# usb2ax_pro_main_v1_0.net
KiCad netlist of a schematic drawn in EAGLE
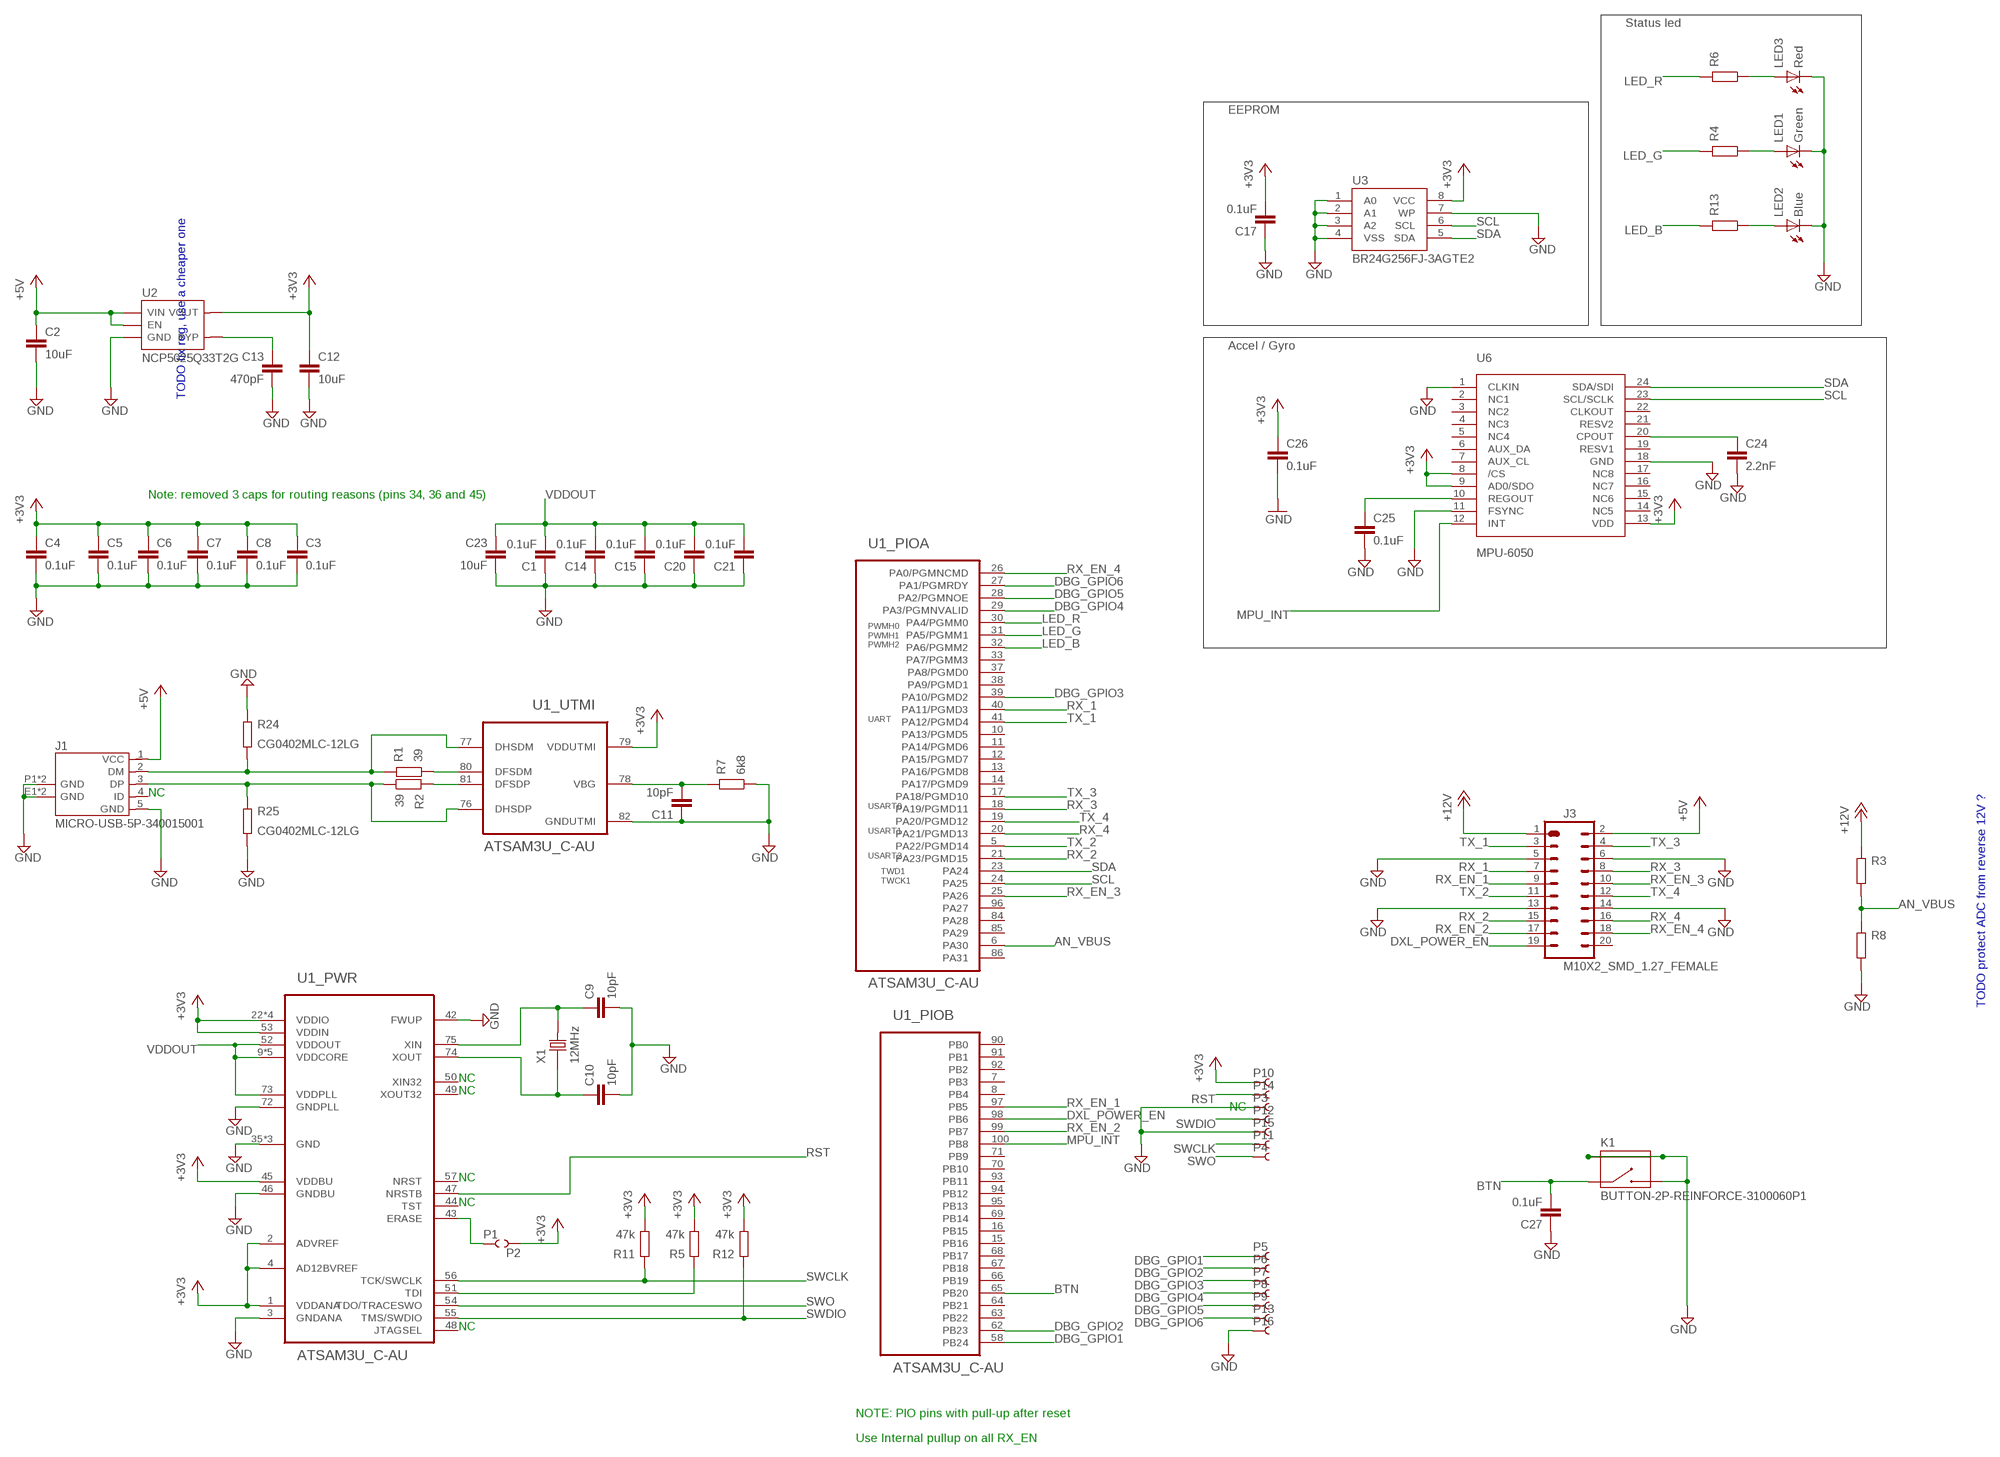
[diagram p0: schematic, sheet 1]

(export (version "E")
  (design (tool "Eeschema 10.0.6"))
  (components
    (comp (ref "C1")
      (value "0.1uF")
      (footprint "eagle-import:0201_N")
      (libsource (lib "eagle-import") (part "C0201"))
    )
    (comp (ref "C2")
      (value "10uF")
      (footprint "eagle-import:0805_N")
      (libsource (lib "eagle-import") (part "C0805"))
    )
    (comp (ref "C3")
      (value "0.1uF")
      (footprint "eagle-import:0201_N")
      (libsource (lib "eagle-import") (part "C0201"))
    )
    (comp (ref "C4")
      (value "0.1uF")
      (footprint "eagle-import:0201_N")
      (libsource (lib "eagle-import") (part "C0201"))
    )
    (comp (ref "C5")
      (value "0.1uF")
      (footprint "eagle-import:0201_N")
      (libsource (lib "eagle-import") (part "C0201"))
    )
    (comp (ref "C6")
      (value "0.1uF")
      (footprint "eagle-import:0201_N")
      (libsource (lib "eagle-import") (part "C0201"))
    )
    (comp (ref "C7")
      (value "0.1uF")
      (footprint "eagle-import:0201_N")
      (libsource (lib "eagle-import") (part "C0201"))
    )
    (comp (ref "C8")
      (value "0.1uF")
      (footprint "eagle-import:0201_N")
      (libsource (lib "eagle-import") (part "C0201"))
    )
    (comp (ref "C9")
      (value "10pF")
      (footprint "eagle-import:0201_N")
      (libsource (lib "eagle-import") (part "C0201"))
    )
    (comp (ref "C10")
      (value "10pF")
      (footprint "eagle-import:0201_N")
      (libsource (lib "eagle-import") (part "C0201"))
    )
    (comp (ref "C11")
      (value "10pF")
      (footprint "eagle-import:0201_N")
      (libsource (lib "eagle-import") (part "C0201"))
    )
    (comp (ref "C12")
      (value "10uF")
      (footprint "eagle-import:0805_N")
      (libsource (lib "eagle-import") (part "C0805"))
    )
    (comp (ref "C13")
      (value "470pF")
      (footprint "eagle-import:0201_N")
      (libsource (lib "eagle-import") (part "C0201"))
    )
    (comp (ref "C14")
      (value "0.1uF")
      (footprint "eagle-import:0201_N")
      (libsource (lib "eagle-import") (part "C0201"))
    )
    (comp (ref "C15")
      (value "0.1uF")
      (footprint "eagle-import:0201_N")
      (libsource (lib "eagle-import") (part "C0201"))
    )
    (comp (ref "C17")
      (value "0.1uF")
      (footprint "eagle-import:0201_N")
      (libsource (lib "eagle-import") (part "C0201"))
    )
    (comp (ref "C20")
      (value "0.1uF")
      (footprint "eagle-import:0201_N")
      (libsource (lib "eagle-import") (part "C0201"))
    )
    (comp (ref "C21")
      (value "0.1uF")
      (footprint "eagle-import:0201_N")
      (libsource (lib "eagle-import") (part "C0201"))
    )
    (comp (ref "C23")
      (value "10uF")
      (footprint "eagle-import:0805_N")
      (libsource (lib "eagle-import") (part "C0805"))
    )
    (comp (ref "C24")
      (value "2.2nF")
      (footprint "eagle-import:0201_N")
      (libsource (lib "eagle-import") (part "C0201"))
    )
    (comp (ref "C25")
      (value "0.1uF")
      (footprint "eagle-import:0201_N")
      (libsource (lib "eagle-import") (part "C0201"))
    )
    (comp (ref "C26")
      (value "0.1uF")
      (footprint "eagle-import:0201_N")
      (libsource (lib "eagle-import") (part "C0201"))
    )
    (comp (ref "C27")
      (value "0.1uF")
      (footprint "eagle-import:0201_N")
      (libsource (lib "eagle-import") (part "C0201"))
    )
    (comp (ref "J1")
      (value "MICRO-USB-5P-340015001")
      (footprint "eagle-import:B-SMD-5P")
      (libsource (lib "eagle-import") (part "MICRO-USB-5P-340015001"))
    )
    (comp (ref "J3")
      (value "M10X2_SMD_1.27_FEMALE")
      (footprint "eagle-import:2X10_SMD_1.27_FEMALE")
      (libsource (lib "eagle-import") (part "M10X2_SMD_1.27_FEMALE"))
    )
    (comp (ref "K1")
      (value "BUTTON-2P-REINFORCE-3100060P1")
      (footprint "eagle-import:4P-SMD-7.0X3.5X3.5H-90D")
      (libsource (lib "eagle-import") (part "BUTTON-2P-REINFORCE-3100060P1"))
    )
    (comp (ref "LED1")
      (value "Green")
      (footprint "eagle-import:D_0603_N")
      (libsource (lib "eagle-import") (part "LED0603"))
    )
    (comp (ref "LED2")
      (value "Blue")
      (footprint "eagle-import:D_0603_N")
      (libsource (lib "eagle-import") (part "LED0603"))
    )
    (comp (ref "LED3")
      (value "Red")
      (footprint "eagle-import:D_0603_N")
      (libsource (lib "eagle-import") (part "LED0603"))
    )
    (comp (ref "P1")
      (value "PIN_SMD_2X2.5")
      (footprint "eagle-import:PIN_SMD_2X2.5")
      (libsource (lib "eagle-import") (part "PIN_SMD_2X2.5"))
    )
    (comp (ref "P2")
      (value "PIN_SMD_2X2.5")
      (footprint "eagle-import:PIN_SMD_2X2.5")
      (libsource (lib "eagle-import") (part "PIN_SMD_2X2.5"))
    )
    (comp (ref "P3")
      (value "PIN_SMD_0.8X1.6")
      (footprint "eagle-import:PIN_SMD_0.8X1.6")
      (libsource (lib "eagle-import") (part "PIN_SMD_0.8X1.6"))
    )
    (comp (ref "P4")
      (value "PIN_SMD_0.8X1.6")
      (footprint "eagle-import:PIN_SMD_0.8X1.6")
      (libsource (lib "eagle-import") (part "PIN_SMD_0.8X1.6"))
    )
    (comp (ref "P5")
      (value "PIN_SMD_1X2")
      (footprint "eagle-import:PIN_SMD_1X2")
      (libsource (lib "eagle-import") (part "PIN_SMD_1X2"))
    )
    (comp (ref "P6")
      (value "PIN_SMD_1X2")
      (footprint "eagle-import:PIN_SMD_1X2")
      (libsource (lib "eagle-import") (part "PIN_SMD_1X2"))
    )
    (comp (ref "P7")
      (value "PIN_SMD_1X2")
      (footprint "eagle-import:PIN_SMD_1X2")
      (libsource (lib "eagle-import") (part "PIN_SMD_1X2"))
    )
    (comp (ref "P8")
      (value "PIN_SMD_1X2")
      (footprint "eagle-import:PIN_SMD_1X2")
      (libsource (lib "eagle-import") (part "PIN_SMD_1X2"))
    )
    (comp (ref "P9")
      (value "PIN_SMD_1X2")
      (footprint "eagle-import:PIN_SMD_1X2")
      (libsource (lib "eagle-import") (part "PIN_SMD_1X2"))
    )
    (comp (ref "P10")
      (value "PIN_SMD_0.8X1.6")
      (footprint "eagle-import:PIN_SMD_0.8X1.6")
      (libsource (lib "eagle-import") (part "PIN_SMD_0.8X1.6"))
    )
    (comp (ref "P11")
      (value "PIN_SMD_0.8X1.6")
      (footprint "eagle-import:PIN_SMD_0.8X1.6")
      (libsource (lib "eagle-import") (part "PIN_SMD_0.8X1.6"))
    )
    (comp (ref "P12")
      (value "PIN_SMD_0.8X1.6")
      (footprint "eagle-import:PIN_SMD_0.8X1.6")
      (libsource (lib "eagle-import") (part "PIN_SMD_0.8X1.6"))
    )
    (comp (ref "P13")
      (value "PIN_SMD_1X2")
      (footprint "eagle-import:PIN_SMD_1X2")
      (libsource (lib "eagle-import") (part "PIN_SMD_1X2"))
    )
    (comp (ref "P14")
      (value "PIN_SMD_0.8X1.6")
      (footprint "eagle-import:PIN_SMD_0.8X1.6")
      (libsource (lib "eagle-import") (part "PIN_SMD_0.8X1.6"))
    )
    (comp (ref "P15")
      (value "PIN_SMD_0.8X1.6")
      (footprint "eagle-import:PIN_SMD_0.8X1.6")
      (libsource (lib "eagle-import") (part "PIN_SMD_0.8X1.6"))
    )
    (comp (ref "P16")
      (value "PIN_SMD_1X2")
      (footprint "eagle-import:PIN_SMD_1X2")
      (libsource (lib "eagle-import") (part "PIN_SMD_1X2"))
    )
    (comp (ref "R1")
      (value "39")
      (footprint "eagle-import:0201_N")
      (libsource (lib "eagle-import") (part "R0201"))
    )
    (comp (ref "R2")
      (value "39")
      (footprint "eagle-import:0201_N")
      (libsource (lib "eagle-import") (part "R0201"))
    )
    (comp (ref "R3")
      (value "R0201")
      (footprint "eagle-import:0201_N")
      (libsource (lib "eagle-import") (part "R0201"))
    )
    (comp (ref "R4")
      (value "R0201")
      (footprint "eagle-import:0201_N")
      (libsource (lib "eagle-import") (part "R0201"))
    )
    (comp (ref "R5")
      (value "47k")
      (footprint "eagle-import:0201_N")
      (libsource (lib "eagle-import") (part "R0201"))
    )
    (comp (ref "R6")
      (value "R0201")
      (footprint "eagle-import:0201_N")
      (libsource (lib "eagle-import") (part "R0201"))
    )
    (comp (ref "R7")
      (value "6k8")
      (footprint "eagle-import:0201_N")
      (libsource (lib "eagle-import") (part "R0201"))
    )
    (comp (ref "R8")
      (value "R0201")
      (footprint "eagle-import:0201_N")
      (libsource (lib "eagle-import") (part "R0201"))
    )
    (comp (ref "R11")
      (value "47k")
      (footprint "eagle-import:0201_N")
      (libsource (lib "eagle-import") (part "R0201"))
    )
    (comp (ref "R12")
      (value "47k")
      (footprint "eagle-import:0201_N")
      (libsource (lib "eagle-import") (part "R0201"))
    )
    (comp (ref "R13")
      (value "R0201")
      (footprint "eagle-import:0201_N")
      (libsource (lib "eagle-import") (part "R0201"))
    )
    (comp (ref "R24")
      (value "CG0402MLC-12LG")
      (footprint "eagle-import:0402_N")
      (libsource (lib "eagle-import") (part "R0402"))
    )
    (comp (ref "R25")
      (value "CG0402MLC-12LG")
      (footprint "eagle-import:0402_N")
      (libsource (lib "eagle-import") (part "R0402"))
    )
    (comp (ref "U1")
      (value "ATSAM3U_C-AU")
      (footprint "eagle-import:QFP50P1600X1600-100N")
      (libsource (lib "eagle-import") (part "ATSAM3U_C-AU"))
    )
    (comp (ref "U2")
      (value "NCP5025Q33T2G")
      (footprint "eagle-import:SC70-5")
      (libsource (lib "eagle-import") (part "MIC5205-3.3YM5"))
    )
    (comp (ref "U3")
      (value "BR24G256FJ-3AGTE2")
      (footprint "eagle-import:SO08")
      (libsource (lib "eagle-import") (part "EEPROM-I2CSMD"))
    )
    (comp (ref "U6")
      (value "MPU-6050")
      (footprint "eagle-import:QFN-24")
      (libsource (lib "eagle-import") (part "MPU-6000"))
    )
    (comp (ref "X1")
      (value "12MHz")
      (footprint "eagle-import:2P-SMD-5.0X3.2")
      (libsource (lib "eagle-import") (part "CRYSTAL-0500290P1"))
    )
  )
  (nets
    (net (code "1") (name "+3V3") (class "Default")
      (node (ref "C12") (pin "1") (pinfunction "1_1") (pintype "passive"))
      (node (ref "C17") (pin "2") (pinfunction "2_2") (pintype "passive"))
      (node (ref "C26") (pin "1") (pinfunction "1_1") (pintype "passive"))
      (node (ref "C3") (pin "1") (pinfunction "1_1") (pintype "passive"))
      (node (ref "C4") (pin "1") (pinfunction "1_1") (pintype "passive"))
      (node (ref "C5") (pin "1") (pinfunction "1_1") (pintype "passive"))
      (node (ref "C6") (pin "1") (pinfunction "1_1") (pintype "passive"))
      (node (ref "C7") (pin "1") (pinfunction "1_1") (pintype "passive"))
      (node (ref "C8") (pin "1") (pinfunction "1_1") (pintype "passive"))
      (node (ref "P10") (pin "PIN") (pinfunction "1_PIN") (pintype "bidirectional"))
      (node (ref "P2") (pin "PIN") (pinfunction "1_PIN") (pintype "bidirectional"))
      (node (ref "R11") (pin "1") (pinfunction "1_1") (pintype "passive"))
      (node (ref "R12") (pin "1") (pinfunction "1_1") (pintype "passive"))
      (node (ref "R5") (pin "1") (pinfunction "1_1") (pintype "passive"))
      (node (ref "U1") (pin "1") (pinfunction "VDDANA_1") (pintype "power_in"))
      (node (ref "U1") (pin "2") (pinfunction "ADVREF_2") (pintype "input"))
      (node (ref "U1") (pin "22") (pinfunction "VDDIO_22") (pintype "power_in"))
      (node (ref "U1") (pin "36") (pinfunction "VDDIO_36") (pintype "power_in"))
      (node (ref "U1") (pin "4") (pinfunction "AD12BVREF_4") (pintype "passive"))
      (node (ref "U1") (pin "45") (pinfunction "VDDBU_45") (pintype "power_in"))
      (node (ref "U1") (pin "53") (pinfunction "VDDIN_53") (pintype "power_in"))
      (node (ref "U1") (pin "60") (pinfunction "VDDIO_60") (pintype "power_in"))
      (node (ref "U1") (pin "79") (pinfunction "VDDUTMI_79") (pintype "power_in"))
      (node (ref "U1") (pin "88") (pinfunction "VDDIO_88") (pintype "power_in"))
      (node (ref "U2") (pin "5") (pinfunction "VOUT_5") (pintype "bidirectional"))
      (node (ref "U3") (pin "8") (pinfunction "VCC_8") (pintype "power_in"))
      (node (ref "U6") (pin "13") (pinfunction "VDD_13") (pintype "bidirectional"))
      (node (ref "U6") (pin "8") (pinfunction "/CS_8") (pintype "bidirectional"))
      (node (ref "U6") (pin "9") (pinfunction "AD0/SDO_9") (pintype "bidirectional"))
    )
    (net (code "2") (name "+5V") (class "Default")
      (node (ref "C2") (pin "1") (pinfunction "1_1") (pintype "passive"))
      (node (ref "J1") (pin "1") (pinfunction "VCC_1") (pintype "bidirectional"))
      (node (ref "J3") (pin "2") (pinfunction "2_2") (pintype "passive"))
      (node (ref "U2") (pin "1") (pinfunction "VIN_1") (pintype "bidirectional"))
      (node (ref "U2") (pin "3") (pinfunction "EN_3") (pintype "bidirectional"))
    )
    (net (code "3") (name "+12V") (class "Default")
      (node (ref "J3") (pin "1") (pinfunction "1_1") (pintype "passive"))
      (node (ref "R3") (pin "2") (pinfunction "2_2") (pintype "passive"))
    )
    (net (code "4") (name "/AN_VBUS") (class "Default")
      (node (ref "R3") (pin "1") (pinfunction "1_1") (pintype "passive"))
      (node (ref "R8") (pin "2") (pinfunction "2_2") (pintype "passive"))
      (node (ref "U1") (pin "6") (pinfunction "PA30_6") (pintype "bidirectional"))
    )
    (net (code "5") (name "/BTN") (class "Default")
      (node (ref "C27") (pin "2") (pinfunction "2_2") (pintype "passive"))
      (node (ref "K1") (pin "1") (pinfunction "1_1") (pintype "bidirectional"))
      (node (ref "U1") (pin "65") (pinfunction "PB20_65") (pintype "bidirectional"))
    )
    (net (code "6") (name "/DBG_GPIO1") (class "Default")
      (node (ref "P5") (pin "P$1") (pinfunction "1_P$1") (pintype "bidirectional"))
      (node (ref "U1") (pin "58") (pinfunction "PB24_58") (pintype "bidirectional"))
    )
    (net (code "7") (name "/DBG_GPIO2") (class "Default")
      (node (ref "P6") (pin "P$1") (pinfunction "1_P$1") (pintype "bidirectional"))
      (node (ref "U1") (pin "62") (pinfunction "PB23_62") (pintype "bidirectional"))
    )
    (net (code "8") (name "/DBG_GPIO3") (class "Default")
      (node (ref "P7") (pin "P$1") (pinfunction "1_P$1") (pintype "bidirectional"))
      (node (ref "U1") (pin "39") (pinfunction "PA10/PGMD2_39") (pintype "bidirectional"))
    )
    (net (code "9") (name "/DBG_GPIO4") (class "Default")
      (node (ref "P8") (pin "P$1") (pinfunction "1_P$1") (pintype "bidirectional"))
      (node (ref "U1") (pin "29") (pinfunction "PA3/PGMNVALID_29") (pintype "bidirectional"))
    )
    (net (code "10") (name "/DBG_GPIO5") (class "Default")
      (node (ref "P9") (pin "P$1") (pinfunction "1_P$1") (pintype "bidirectional"))
      (node (ref "U1") (pin "28") (pinfunction "PA2/PGMNOE_28") (pintype "bidirectional"))
    )
    (net (code "11") (name "/DBG_GPIO6") (class "Default")
      (node (ref "P13") (pin "P$1") (pinfunction "1_P$1") (pintype "bidirectional"))
      (node (ref "U1") (pin "27") (pinfunction "PA1/PGMRDY_27") (pintype "bidirectional"))
    )
    (net (code "12") (name "/DXL_POWER_EN") (class "Default")
      (node (ref "J3") (pin "19") (pinfunction "19_19") (pintype "passive"))
      (node (ref "U1") (pin "98") (pinfunction "PB6_98") (pintype "bidirectional"))
    )
    (net (code "13") (name "/LED_B") (class "Default")
      (node (ref "R13") (pin "2") (pinfunction "2_2") (pintype "passive"))
      (node (ref "U1") (pin "32") (pinfunction "PA6/PGMM2_32") (pintype "bidirectional"))
    )
    (net (code "14") (name "/LED_G") (class "Default")
      (node (ref "R4") (pin "2") (pinfunction "2_2") (pintype "passive"))
      (node (ref "U1") (pin "31") (pinfunction "PA5/PGMM1_31") (pintype "bidirectional"))
    )
    (net (code "15") (name "/LED_R") (class "Default")
      (node (ref "R6") (pin "2") (pinfunction "2_2") (pintype "passive"))
      (node (ref "U1") (pin "30") (pinfunction "PA4/PGMM0_30") (pintype "bidirectional"))
    )
    (net (code "16") (name "/MPU_INT") (class "Default")
      (node (ref "U1") (pin "100") (pinfunction "PB8_100") (pintype "bidirectional"))
      (node (ref "U6") (pin "12") (pinfunction "INT_12") (pintype "bidirectional"))
    )
    (net (code "17") (name "/RST") (class "Default")
      (node (ref "P14") (pin "PIN") (pinfunction "1_PIN") (pintype "bidirectional"))
      (node (ref "U1") (pin "47") (pinfunction "NRSTB_47") (pintype "input"))
    )
    (net (code "18") (name "/RX_1") (class "Default")
      (node (ref "J3") (pin "7") (pinfunction "7_7") (pintype "passive"))
      (node (ref "U1") (pin "40") (pinfunction "PA11/PGMD3_40") (pintype "bidirectional"))
    )
    (net (code "19") (name "/RX_2") (class "Default")
      (node (ref "J3") (pin "15") (pinfunction "15_15") (pintype "passive"))
      (node (ref "U1") (pin "21") (pinfunction "PA23/PGMD15_21") (pintype "bidirectional"))
    )
    (net (code "20") (name "/RX_3") (class "Default")
      (node (ref "J3") (pin "8") (pinfunction "8_8") (pintype "passive"))
      (node (ref "U1") (pin "18") (pinfunction "PA19/PGMD11_18") (pintype "bidirectional"))
    )
    (net (code "21") (name "/RX_4") (class "Default")
      (node (ref "J3") (pin "16") (pinfunction "16_16") (pintype "passive"))
      (node (ref "U1") (pin "20") (pinfunction "PA21/PGMD13_20") (pintype "bidirectional"))
    )
    (net (code "22") (name "/RX_EN_1") (class "Default")
      (node (ref "J3") (pin "9") (pinfunction "9_9") (pintype "passive"))
      (node (ref "U1") (pin "97") (pinfunction "PB5_97") (pintype "bidirectional"))
    )
    (net (code "23") (name "/RX_EN_2") (class "Default")
      (node (ref "J3") (pin "17") (pinfunction "17_17") (pintype "passive"))
      (node (ref "U1") (pin "99") (pinfunction "PB7_99") (pintype "bidirectional"))
    )
    (net (code "24") (name "/RX_EN_3") (class "Default")
      (node (ref "J3") (pin "10") (pinfunction "10_10") (pintype "passive"))
      (node (ref "U1") (pin "25") (pinfunction "PA26_25") (pintype "bidirectional"))
    )
    (net (code "25") (name "/RX_EN_4") (class "Default")
      (node (ref "J3") (pin "18") (pinfunction "18_18") (pintype "passive"))
      (node (ref "U1") (pin "26") (pinfunction "PA0/PGMNCMD_26") (pintype "bidirectional"))
    )
    (net (code "26") (name "/SCL") (class "Default")
      (node (ref "U1") (pin "24") (pinfunction "PA25_24") (pintype "bidirectional"))
      (node (ref "U3") (pin "6") (pinfunction "SCL_6") (pintype "bidirectional"))
      (node (ref "U6") (pin "23") (pinfunction "SCL/SCLK_23") (pintype "bidirectional"))
    )
    (net (code "27") (name "/SDA") (class "Default")
      (node (ref "U1") (pin "23") (pinfunction "PA24_23") (pintype "bidirectional"))
      (node (ref "U3") (pin "5") (pinfunction "SDA_5") (pintype "bidirectional"))
      (node (ref "U6") (pin "24") (pinfunction "SDA/SDI_24") (pintype "bidirectional"))
    )
    (net (code "28") (name "/SWCLK") (class "Default")
      (node (ref "P11") (pin "PIN") (pinfunction "1_PIN") (pintype "bidirectional"))
      (node (ref "R11") (pin "2") (pinfunction "2_2") (pintype "passive"))
      (node (ref "U1") (pin "56") (pinfunction "TCK/SWCLK_56") (pintype "input"))
    )
    (net (code "29") (name "/SWDIO") (class "Default")
      (node (ref "P12") (pin "PIN") (pinfunction "1_PIN") (pintype "bidirectional"))
      (node (ref "R12") (pin "2") (pinfunction "2_2") (pintype "passive"))
      (node (ref "U1") (pin "55") (pinfunction "TMS/SWDIO_55") (pintype "bidirectional"))
    )
    (net (code "30") (name "/SWO") (class "Default")
      (node (ref "P4") (pin "PIN") (pinfunction "1_PIN") (pintype "bidirectional"))
      (node (ref "U1") (pin "54") (pinfunction "TDO/TRACESWO_54") (pintype "output"))
    )
    (net (code "31") (name "/TX_1") (class "Default")
      (node (ref "J3") (pin "3") (pinfunction "3_3") (pintype "passive"))
      (node (ref "U1") (pin "41") (pinfunction "PA12/PGMD4_41") (pintype "bidirectional"))
    )
    (net (code "32") (name "/TX_2") (class "Default")
      (node (ref "J3") (pin "11") (pinfunction "11_11") (pintype "passive"))
      (node (ref "U1") (pin "5") (pinfunction "PA22/PGMD14_5") (pintype "bidirectional"))
    )
    (net (code "33") (name "/TX_3") (class "Default")
      (node (ref "J3") (pin "4") (pinfunction "4_4") (pintype "passive"))
      (node (ref "U1") (pin "17") (pinfunction "PA18/PGMD10_17") (pintype "bidirectional"))
    )
    (net (code "34") (name "/TX_4") (class "Default")
      (node (ref "J3") (pin "12") (pinfunction "12_12") (pintype "passive"))
      (node (ref "U1") (pin "19") (pinfunction "PA20/PGMD12_19") (pintype "bidirectional"))
    )
    (net (code "35") (name "/VDDOUT") (class "Default")
      (node (ref "C1") (pin "2") (pinfunction "2_2") (pintype "passive"))
      (node (ref "C14") (pin "2") (pinfunction "2_2") (pintype "passive"))
      (node (ref "C15") (pin "2") (pinfunction "2_2") (pintype "passive"))
      (node (ref "C20") (pin "2") (pinfunction "2_2") (pintype "passive"))
      (node (ref "C21") (pin "2") (pinfunction "2_2") (pintype "passive"))
      (node (ref "C23") (pin "1") (pinfunction "1_1") (pintype "passive"))
      (node (ref "U1") (pin "34") (pinfunction "VDDCORE_34") (pintype "power_in"))
      (node (ref "U1") (pin "52") (pinfunction "VDDOUT_52") (pintype "power_in"))
      (node (ref "U1") (pin "59") (pinfunction "VDDCORE_59") (pintype "power_in"))
      (node (ref "U1") (pin "73") (pinfunction "VDDPLL_73") (pintype "power_in"))
      (node (ref "U1") (pin "83") (pinfunction "VDDCORE_83") (pintype "power_in"))
      (node (ref "U1") (pin "87") (pinfunction "VDDCORE_87") (pintype "power_in"))
      (node (ref "U1") (pin "9") (pinfunction "VDDCORE_9") (pintype "power_in"))
    )
    (net (code "36") (name "GND") (class "Default")
      (node (ref "C1") (pin "1") (pinfunction "1_1") (pintype "passive"))
      (node (ref "C10") (pin "2") (pinfunction "2_2") (pintype "passive"))
      (node (ref "C11") (pin "1") (pinfunction "1_1") (pintype "passive"))
      (node (ref "C12") (pin "2") (pinfunction "2_2") (pintype "passive"))
      (node (ref "C13") (pin "2") (pinfunction "2_2") (pintype "passive"))
      (node (ref "C14") (pin "1") (pinfunction "1_1") (pintype "passive"))
      (node (ref "C15") (pin "1") (pinfunction "1_1") (pintype "passive"))
      (node (ref "C17") (pin "1") (pinfunction "1_1") (pintype "passive"))
      (node (ref "C2") (pin "2") (pinfunction "2_2") (pintype "passive"))
      (node (ref "C20") (pin "1") (pinfunction "1_1") (pintype "passive"))
      (node (ref "C21") (pin "1") (pinfunction "1_1") (pintype "passive"))
      (node (ref "C23") (pin "2") (pinfunction "2_2") (pintype "passive"))
      (node (ref "C24") (pin "2") (pinfunction "2_2") (pintype "passive"))
      (node (ref "C25") (pin "2") (pinfunction "2_2") (pintype "passive"))
      (node (ref "C26") (pin "2") (pinfunction "2_2") (pintype "passive"))
      (node (ref "C27") (pin "1") (pinfunction "1_1") (pintype "passive"))
      (node (ref "C3") (pin "2") (pinfunction "2_2") (pintype "passive"))
      (node (ref "C4") (pin "2") (pinfunction "2_2") (pintype "passive"))
      (node (ref "C5") (pin "2") (pinfunction "2_2") (pintype "passive"))
      (node (ref "C6") (pin "2") (pinfunction "2_2") (pintype "passive"))
      (node (ref "C7") (pin "2") (pinfunction "2_2") (pintype "passive"))
      (node (ref "C8") (pin "2") (pinfunction "2_2") (pintype "passive"))
      (node (ref "C9") (pin "2") (pinfunction "2_2") (pintype "passive"))
      (node (ref "J1") (pin "5") (pinfunction "GND_5") (pintype "bidirectional"))
      (node (ref "J1") (pin "E1") (pinfunction "GND_E1") (pintype "bidirectional"))
      (node (ref "J1") (pin "E2") (pinfunction "GND_E2") (pintype "bidirectional"))
      (node (ref "J1") (pin "P1") (pinfunction "GND_P1") (pintype "bidirectional"))
      (node (ref "J1") (pin "P2") (pinfunction "GND_P2") (pintype "bidirectional"))
      (node (ref "J3") (pin "13") (pinfunction "13_13") (pintype "passive"))
      (node (ref "J3") (pin "14") (pinfunction "14_14") (pintype "passive"))
      (node (ref "J3") (pin "5") (pinfunction "5_5") (pintype "passive"))
      (node (ref "J3") (pin "6") (pinfunction "6_6") (pintype "passive"))
      (node (ref "K1") (pin "2") (pinfunction "2_2") (pintype "bidirectional"))
      (node (ref "K1") (pin "S1") (pinfunction "S1_S1") (pintype "bidirectional"))
      (node (ref "K1") (pin "S2") (pinfunction "S2_S2") (pintype "bidirectional"))
      (node (ref "LED1") (pin "C") (pinfunction "C_C") (pintype "passive"))
      (node (ref "LED2") (pin "C") (pinfunction "C_C") (pintype "passive"))
      (node (ref "LED3") (pin "C") (pinfunction "C_C") (pintype "passive"))
      (node (ref "P15") (pin "PIN") (pinfunction "1_PIN") (pintype "bidirectional"))
      (node (ref "P16") (pin "P$1") (pinfunction "1_P$1") (pintype "bidirectional"))
      (node (ref "P3") (pin "PIN") (pinfunction "1_PIN") (pintype "bidirectional"))
      (node (ref "R24") (pin "2") (pinfunction "2_2") (pintype "passive"))
      (node (ref "R25") (pin "1") (pinfunction "1_1") (pintype "passive"))
      (node (ref "R7") (pin "1") (pinfunction "1_1") (pintype "passive"))
      (node (ref "R8") (pin "1") (pinfunction "1_1") (pintype "passive"))
      (node (ref "U1") (pin "3") (pinfunction "GNDANA_3") (pintype "passive"))
      (node (ref "U1") (pin "35") (pinfunction "GND_35") (pintype "passive"))
      (node (ref "U1") (pin "42") (pinfunction "FWUP_42") (pintype "input"))
      (node (ref "U1") (pin "46") (pinfunction "GNDBU_46") (pintype "passive"))
      (node (ref "U1") (pin "61") (pinfunction "GND_61") (pintype "passive"))
      (node (ref "U1") (pin "72") (pinfunction "GNDPLL_72") (pintype "passive"))
      (node (ref "U1") (pin "82") (pinfunction "GNDUTMI_82") (pintype "passive"))
      (node (ref "U1") (pin "89") (pinfunction "GND_89") (pintype "passive"))
      (node (ref "U2") (pin "2") (pinfunction "GND_2") (pintype "bidirectional"))
      (node (ref "U3") (pin "1") (pinfunction "A0_1") (pintype "bidirectional"))
      (node (ref "U3") (pin "2") (pinfunction "A1_2") (pintype "bidirectional"))
      (node (ref "U3") (pin "3") (pinfunction "A2_3") (pintype "bidirectional"))
      (node (ref "U3") (pin "4") (pinfunction "VSS_4") (pintype "power_in"))
      (node (ref "U3") (pin "7") (pinfunction "WP_7") (pintype "bidirectional"))
      (node (ref "U6") (pin "1") (pinfunction "CLKIN_1") (pintype "bidirectional"))
      (node (ref "U6") (pin "11") (pinfunction "FSYNC_11") (pintype "bidirectional"))
      (node (ref "U6") (pin "18") (pinfunction "GND_18") (pintype "bidirectional"))
    )
    (net (code "37") (name "Net-(J1-DM)") (class "Default")
      (node (ref "J1") (pin "2") (pinfunction "DM_2") (pintype "bidirectional"))
      (node (ref "R1") (pin "2") (pinfunction "2_2") (pintype "passive"))
      (node (ref "R24") (pin "1") (pinfunction "1_1") (pintype "passive"))
      (node (ref "U1") (pin "77") (pinfunction "DHSDM_77") (pintype "bidirectional"))
    )
    (net (code "38") (name "Net-(J1-DP)") (class "Default")
      (node (ref "J1") (pin "3") (pinfunction "DP_3") (pintype "bidirectional"))
      (node (ref "R2") (pin "1") (pinfunction "1_1") (pintype "passive"))
      (node (ref "R25") (pin "2") (pinfunction "2_2") (pintype "passive"))
      (node (ref "U1") (pin "76") (pinfunction "DHSDP_76") (pintype "bidirectional"))
    )
    (net (code "39") (name "Net-(LED1-PadA)") (class "Default")
      (node (ref "LED1") (pin "A") (pinfunction "A_A") (pintype "passive"))
      (node (ref "R4") (pin "1") (pinfunction "1_1") (pintype "passive"))
    )
    (net (code "40") (name "Net-(LED2-PadA)") (class "Default")
      (node (ref "LED2") (pin "A") (pinfunction "A_A") (pintype "passive"))
      (node (ref "R13") (pin "1") (pinfunction "1_1") (pintype "passive"))
    )
    (net (code "41") (name "Net-(LED3-PadA)") (class "Default")
      (node (ref "LED3") (pin "A") (pinfunction "A_A") (pintype "passive"))
      (node (ref "R6") (pin "1") (pinfunction "1_1") (pintype "passive"))
    )
    (net (code "42") (name "Net-(P1-1)") (class "Default")
      (node (ref "P1") (pin "PIN") (pinfunction "1_PIN") (pintype "bidirectional"))
      (node (ref "U1") (pin "43") (pinfunction "ERASE_43") (pintype "input"))
    )
    (net (code "43") (name "Net-(U1C-TDI)") (class "Default")
      (node (ref "R5") (pin "2") (pinfunction "2_2") (pintype "passive"))
      (node (ref "U1") (pin "51") (pinfunction "TDI_51") (pintype "input"))
    )
    (net (code "44") (name "Net-(U1C-XIN)") (class "Default")
      (node (ref "C9") (pin "1") (pinfunction "1_1") (pintype "passive"))
      (node (ref "U1") (pin "75") (pinfunction "XIN_75") (pintype "input"))
      (node (ref "X1") (pin "2") (pinfunction "2_2") (pintype "passive"))
    )
    (net (code "45") (name "Net-(U1C-XOUT)") (class "Default")
      (node (ref "C10") (pin "1") (pinfunction "1_1") (pintype "passive"))
      (node (ref "U1") (pin "74") (pinfunction "XOUT_74") (pintype "output"))
      (node (ref "X1") (pin "1") (pinfunction "1_1") (pintype "passive"))
    )
    (net (code "46") (name "Net-(U1D-DFSDM)") (class "Default")
      (node (ref "R1") (pin "1") (pinfunction "1_1") (pintype "passive"))
      (node (ref "U1") (pin "80") (pinfunction "DFSDM_80") (pintype "bidirectional"))
    )
    (net (code "47") (name "Net-(U1D-DFSDP)") (class "Default")
      (node (ref "R2") (pin "2") (pinfunction "2_2") (pintype "passive"))
      (node (ref "U1") (pin "81") (pinfunction "DFSDP_81") (pintype "bidirectional"))
    )
    (net (code "48") (name "Net-(U1D-VBG)") (class "Default")
      (node (ref "C11") (pin "2") (pinfunction "2_2") (pintype "passive"))
      (node (ref "R7") (pin "2") (pinfunction "2_2") (pintype "passive"))
      (node (ref "U1") (pin "78") (pinfunction "VBG_78") (pintype "bidirectional"))
    )
    (net (code "49") (name "Net-(U2-BYP)") (class "Default")
      (node (ref "C13") (pin "1") (pinfunction "1_1") (pintype "passive"))
      (node (ref "U2") (pin "4") (pinfunction "BYP_4") (pintype "bidirectional"))
    )
    (net (code "50") (name "Net-(U6-CPOUT)") (class "Default")
      (node (ref "C24") (pin "1") (pinfunction "1_1") (pintype "passive"))
      (node (ref "U6") (pin "20") (pinfunction "CPOUT_20") (pintype "bidirectional"))
    )
    (net (code "51") (name "Net-(U6-REGOUT)") (class "Default")
      (node (ref "C25") (pin "1") (pinfunction "1_1") (pintype "passive"))
      (node (ref "U6") (pin "10") (pinfunction "REGOUT_10") (pintype "bidirectional"))
    )
    (net (code "52") (name "unconnected-(J1-ID-Pad4)") (class "Default")
      (node (ref "J1") (pin "4") (pinfunction "ID_4") (pintype "bidirectional"))
    )
    (net (code "53") (name "unconnected-(J3-Pad20)") (class "Default")
      (node (ref "J3") (pin "20") (pinfunction "20_20") (pintype "passive"))
    )
    (net (code "54") (name "unconnected-(U1A-PA7{slash}PGMM3-Pad33)") (class "Default")
      (node (ref "U1") (pin "33") (pinfunction "PA7/PGMM3_33") (pintype "bidirectional"))
    )
    (net (code "55") (name "unconnected-(U1A-PA8{slash}PGMD0-Pad37)") (class "Default")
      (node (ref "U1") (pin "37") (pinfunction "PA8/PGMD0_37") (pintype "bidirectional"))
    )
    (net (code "56") (name "unconnected-(U1A-PA9{slash}PGMD1-Pad38)") (class "Default")
      (node (ref "U1") (pin "38") (pinfunction "PA9/PGMD1_38") (pintype "bidirectional"))
    )
    (net (code "57") (name "unconnected-(U1A-PA13{slash}PGMD5-Pad10)") (class "Default")
      (node (ref "U1") (pin "10") (pinfunction "PA13/PGMD5_10") (pintype "bidirectional"))
    )
    (net (code "58") (name "unconnected-(U1A-PA14{slash}PGMD6-Pad11)") (class "Default")
      (node (ref "U1") (pin "11") (pinfunction "PA14/PGMD6_11") (pintype "bidirectional"))
    )
    (net (code "59") (name "unconnected-(U1A-PA15{slash}PGMD7-Pad12)") (class "Default")
      (node (ref "U1") (pin "12") (pinfunction "PA15/PGMD7_12") (pintype "bidirectional"))
    )
    (net (code "60") (name "unconnected-(U1A-PA16{slash}PGMD8-Pad13)") (class "Default")
      (node (ref "U1") (pin "13") (pinfunction "PA16/PGMD8_13") (pintype "bidirectional"))
    )
    (net (code "61") (name "unconnected-(U1A-PA17{slash}PGMD9-Pad14)") (class "Default")
      (node (ref "U1") (pin "14") (pinfunction "PA17/PGMD9_14") (pintype "bidirectional"))
    )
    (net (code "62") (name "unconnected-(U1A-PA27-Pad96)") (class "Default")
      (node (ref "U1") (pin "96") (pinfunction "PA27_96") (pintype "bidirectional"))
    )
    (net (code "63") (name "unconnected-(U1A-PA28-Pad84)") (class "Default")
      (node (ref "U1") (pin "84") (pinfunction "PA28_84") (pintype "bidirectional"))
    )
    (net (code "64") (name "unconnected-(U1A-PA29-Pad85)") (class "Default")
      (node (ref "U1") (pin "85") (pinfunction "PA29_85") (pintype "bidirectional"))
    )
    (net (code "65") (name "unconnected-(U1A-PA31-Pad86)") (class "Default")
      (node (ref "U1") (pin "86") (pinfunction "PA31_86") (pintype "bidirectional"))
    )
    (net (code "66") (name "unconnected-(U1B-PB0-Pad90)") (class "Default")
      (node (ref "U1") (pin "90") (pinfunction "PB0_90") (pintype "bidirectional"))
    )
    (net (code "67") (name "unconnected-(U1B-PB1-Pad91)") (class "Default")
      (node (ref "U1") (pin "91") (pinfunction "PB1_91") (pintype "bidirectional"))
    )
    (net (code "68") (name "unconnected-(U1B-PB2-Pad92)") (class "Default")
      (node (ref "U1") (pin "92") (pinfunction "PB2_92") (pintype "bidirectional"))
    )
    (net (code "69") (name "unconnected-(U1B-PB3-Pad7)") (class "Default")
      (node (ref "U1") (pin "7") (pinfunction "PB3_7") (pintype "bidirectional"))
    )
    (net (code "70") (name "unconnected-(U1B-PB4-Pad8)") (class "Default")
      (node (ref "U1") (pin "8") (pinfunction "PB4_8") (pintype "bidirectional"))
    )
    (net (code "71") (name "unconnected-(U1B-PB9-Pad71)") (class "Default")
      (node (ref "U1") (pin "71") (pinfunction "PB9_71") (pintype "bidirectional"))
    )
    (net (code "72") (name "unconnected-(U1B-PB10-Pad70)") (class "Default")
      (node (ref "U1") (pin "70") (pinfunction "PB10_70") (pintype "bidirectional"))
    )
    (net (code "73") (name "unconnected-(U1B-PB11-Pad93)") (class "Default")
      (node (ref "U1") (pin "93") (pinfunction "PB11_93") (pintype "bidirectional"))
    )
    (net (code "74") (name "unconnected-(U1B-PB12-Pad94)") (class "Default")
      (node (ref "U1") (pin "94") (pinfunction "PB12_94") (pintype "bidirectional"))
    )
    (net (code "75") (name "unconnected-(U1B-PB13-Pad95)") (class "Default")
      (node (ref "U1") (pin "95") (pinfunction "PB13_95") (pintype "bidirectional"))
    )
    (net (code "76") (name "unconnected-(U1B-PB14-Pad69)") (class "Default")
      (node (ref "U1") (pin "69") (pinfunction "PB14_69") (pintype "bidirectional"))
    )
    (net (code "77") (name "unconnected-(U1B-PB15-Pad16)") (class "Default")
      (node (ref "U1") (pin "16") (pinfunction "PB15_16") (pintype "bidirectional"))
    )
    (net (code "78") (name "unconnected-(U1B-PB16-Pad15)") (class "Default")
      (node (ref "U1") (pin "15") (pinfunction "PB16_15") (pintype "bidirectional"))
    )
    (net (code "79") (name "unconnected-(U1B-PB17-Pad68)") (class "Default")
      (node (ref "U1") (pin "68") (pinfunction "PB17_68") (pintype "bidirectional"))
    )
    (net (code "80") (name "unconnected-(U1B-PB18-Pad67)") (class "Default")
      (node (ref "U1") (pin "67") (pinfunction "PB18_67") (pintype "bidirectional"))
    )
    (net (code "81") (name "unconnected-(U1B-PB19-Pad66)") (class "Default")
      (node (ref "U1") (pin "66") (pinfunction "PB19_66") (pintype "bidirectional"))
    )
    (net (code "82") (name "unconnected-(U1B-PB21-Pad64)") (class "Default")
      (node (ref "U1") (pin "64") (pinfunction "PB21_64") (pintype "bidirectional"))
    )
    (net (code "83") (name "unconnected-(U1B-PB22-Pad63)") (class "Default")
      (node (ref "U1") (pin "63") (pinfunction "PB22_63") (pintype "bidirectional"))
    )
    (net (code "84") (name "unconnected-(U1C-JTAGSEL-Pad48)") (class "Default")
      (node (ref "U1") (pin "48") (pinfunction "JTAGSEL_48") (pintype "input"))
    )
    (net (code "85") (name "unconnected-(U1C-NRST-Pad57)") (class "Default")
      (node (ref "U1") (pin "57") (pinfunction "NRST_57") (pintype "input"))
    )
    (net (code "86") (name "unconnected-(U1C-TST-Pad44)") (class "Default")
      (node (ref "U1") (pin "44") (pinfunction "TST_44") (pintype "input"))
    )
    (net (code "87") (name "unconnected-(U1C-XIN32-Pad50)") (class "Default")
      (node (ref "U1") (pin "50") (pinfunction "XIN32_50") (pintype "input"))
    )
    (net (code "88") (name "unconnected-(U1C-XOUT32-Pad49)") (class "Default")
      (node (ref "U1") (pin "49") (pinfunction "XOUT32_49") (pintype "output"))
    )
    (net (code "89") (name "unconnected-(U6-AUX_CL-Pad7)") (class "Default")
      (node (ref "U6") (pin "7") (pinfunction "AUX_CL_7") (pintype "bidirectional"))
    )
    (net (code "90") (name "unconnected-(U6-AUX_DA-Pad6)") (class "Default")
      (node (ref "U6") (pin "6") (pinfunction "AUX_DA_6") (pintype "bidirectional"))
    )
    (net (code "91") (name "unconnected-(U6-CLKOUT-Pad22)") (class "Default")
      (node (ref "U6") (pin "22") (pinfunction "CLKOUT_22") (pintype "bidirectional"))
    )
    (net (code "92") (name "unconnected-(U6-NC1-Pad2)") (class "Default")
      (node (ref "U6") (pin "2") (pinfunction "NC1_2") (pintype "bidirectional"))
    )
    (net (code "93") (name "unconnected-(U6-NC2-Pad3)") (class "Default")
      (node (ref "U6") (pin "3") (pinfunction "NC2_3") (pintype "bidirectional"))
    )
    (net (code "94") (name "unconnected-(U6-NC3-Pad4)") (class "Default")
      (node (ref "U6") (pin "4") (pinfunction "NC3_4") (pintype "bidirectional"))
    )
    (net (code "95") (name "unconnected-(U6-NC4-Pad5)") (class "Default")
      (node (ref "U6") (pin "5") (pinfunction "NC4_5") (pintype "bidirectional"))
    )
    (net (code "96") (name "unconnected-(U6-NC5-Pad14)") (class "Default")
      (node (ref "U6") (pin "14") (pinfunction "NC5_14") (pintype "bidirectional"))
    )
    (net (code "97") (name "unconnected-(U6-NC6-Pad15)") (class "Default")
      (node (ref "U6") (pin "15") (pinfunction "NC6_15") (pintype "bidirectional"))
    )
    (net (code "98") (name "unconnected-(U6-NC7-Pad16)") (class "Default")
      (node (ref "U6") (pin "16") (pinfunction "NC7_16") (pintype "bidirectional"))
    )
    (net (code "99") (name "unconnected-(U6-NC8-Pad17)") (class "Default")
      (node (ref "U6") (pin "17") (pinfunction "NC8_17") (pintype "bidirectional"))
    )
    (net (code "100") (name "unconnected-(U6-RESV1-Pad19)") (class "Default")
      (node (ref "U6") (pin "19") (pinfunction "RESV1_19") (pintype "bidirectional"))
    )
    (net (code "101") (name "unconnected-(U6-RESV2-Pad21)") (class "Default")
      (node (ref "U6") (pin "21") (pinfunction "RESV2_21") (pintype "bidirectional"))
    )
  )
)
